# Out.net
KiCad netlist of a schematic drawn in Altium Designer
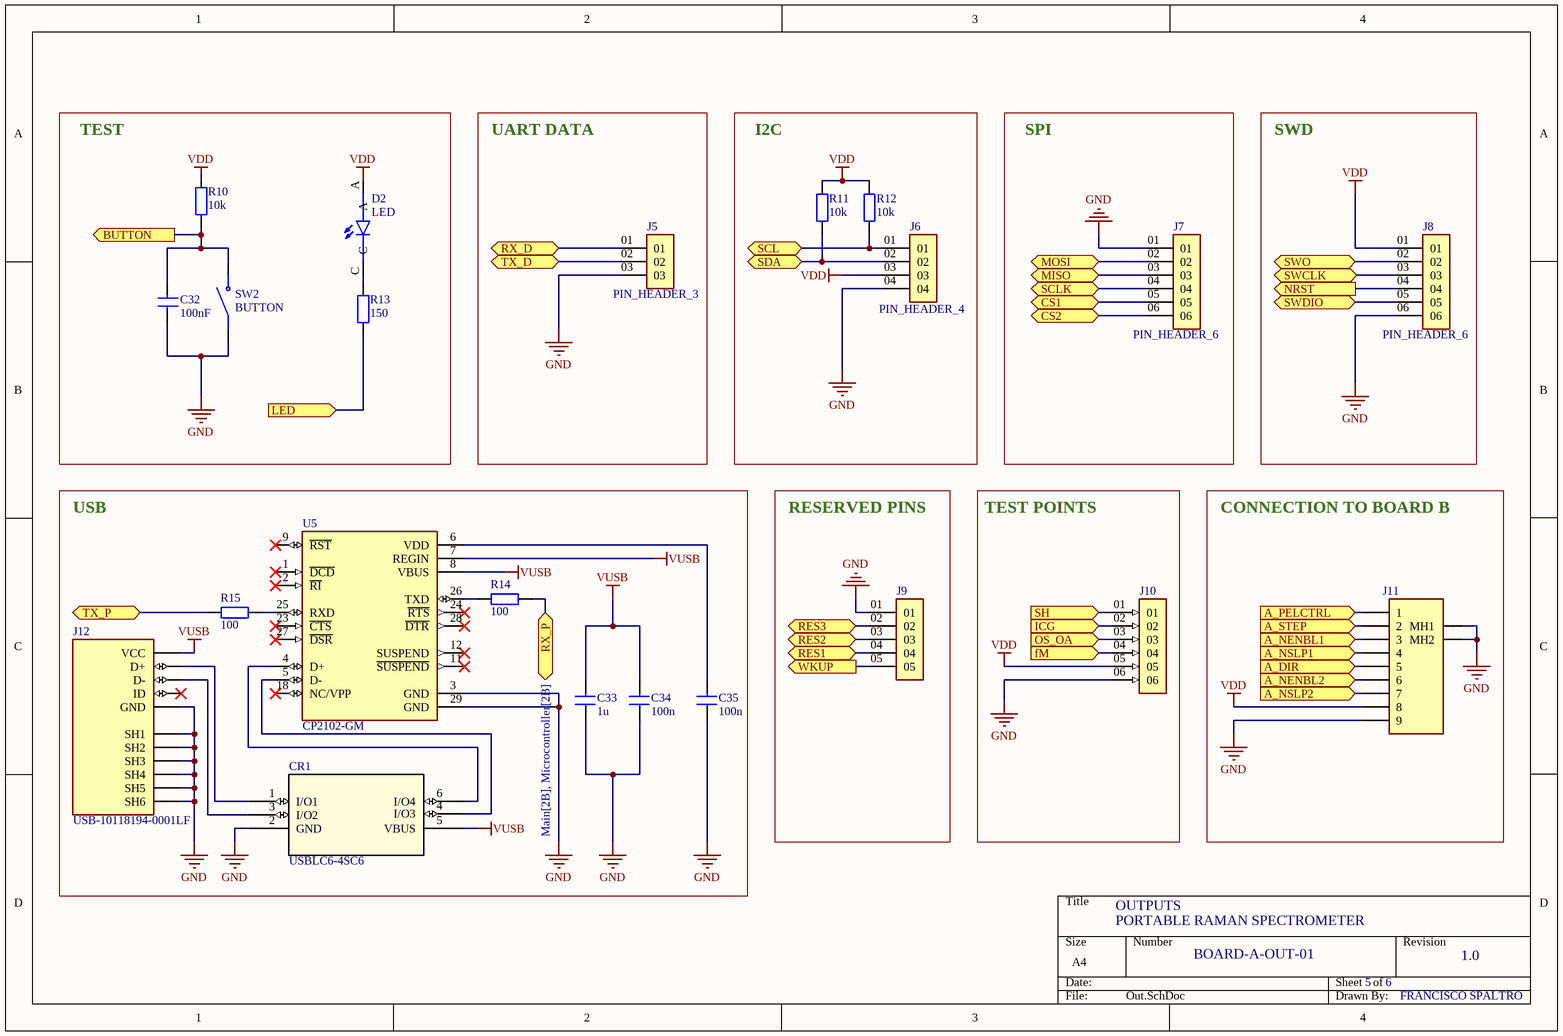
[diagram p0: Out.SchDoc]

(export (version "E")
  (design (tool "Eeschema 10.0.6"))
  (components
    (comp (ref "C32")
      (value "100nF")
      (footprint "RES_0805")
      (description "Generic Capacitor")
      (libsource (lib "Components") (part "CAP_0805"))
    )
    (comp (ref "C33")
      (value "1u")
      (footprint "RES_0805")
      (description "Generic Capacitor")
      (libsource (lib "") (part "CAP_0805_1"))
    )
    (comp (ref "C34")
      (value "100n")
      (footprint "RES_0805")
      (description "Generic Capacitor")
      (libsource (lib "") (part "CAP_0805_1"))
    )
    (comp (ref "C35")
      (value "100n")
      (footprint "RES_0805")
      (description "Generic Capacitor")
      (libsource (lib "") (part "CAP_0805_1"))
    )
    (comp (ref "CR1")
      (value "USBLC6-4SC6")
      (footprint "SOT23-6L_STM-M")
      (description "Very low capacitance ESD protection")
      (fields (field (name "COPYRIGHT") "Copyright (C) 2025 Ultra Librarian. All rights reserved."))
      (libsource (lib "Components") (part "USBLC6-4SC6"))
    )
    (comp (ref "D2")
      (value "LED")
      (footprint "LEDC1608X35N")
      (description "Red 631nm LED Indication - Discrete 2V 0603 (1608 Metric)")
      (fields (field (name "MF") "Lite-On Inc.") (field (name "MP") "LTST-C190KRKT"))
      (libsource (lib "CompAct") (part "LED-LTST-C190KRKT"))
    )
    (comp (ref "J5")
      (value "PIN_HEADER_3")
      (footprint "GEN_PIN3")
      (description "Generic 40 mils drill size, 100 mils step")
      (fields (field (name "MF") "Samtec Inc.") (field (name "MP") "TS-103-T-A"))
      (libsource (lib "Components") (part "PIN_HEADER_3"))
    )
    (comp (ref "J6")
      (value "PIN_HEADER_4")
      (footprint "GEN_PIN4")
      (description "Generic 40 mils drill size, 100 mils step")
      (fields (field (name "MF") "Samtec Inc.") (field (name "MP") "TS-104-T-A"))
      (libsource (lib "Components") (part "PIN_HEADER_4"))
    )
    (comp (ref "J7")
      (value "PIN_HEADER_6")
      (footprint "GEN_PIN6")
      (description "Generic 40 mils drill size, 100 mils step")
      (fields (field (name "MF") "Samtec Inc.") (field (name "MP") "TS-106-T-A"))
      (libsource (lib "Components") (part "PIN_HEADER_6"))
    )
    (comp (ref "J8")
      (value "PIN_HEADER_6")
      (footprint "GEN_PIN6")
      (description "Generic 40 mils drill size, 100 mils step")
      (fields (field (name "MF") "Samtec Inc.") (field (name "MP") "TS-106-T-A"))
      (libsource (lib "Components") (part "PIN_HEADER_6"))
    )
    (comp (ref "J9")
      (value "PIN_HEADER_5")
      (footprint "Components:GEN_PIN5")
      (description "Generic 40 mils drill size, 100 mils step")
      (fields (field (name "MF") "Samtec Inc.") (field (name "MP") "TS-105-T-A"))
      (libsource (lib "Components") (part "PIN_HEADER_5"))
    )
    (comp (ref "J10")
      (value "PIN_HEADER_6")
      (footprint "GEN_PIN6")
      (description "Generic 40 mils drill size, 100 mils step")
      (fields (field (name "MF") "Samtec Inc.") (field (name "MP") "TS-106-T-A"))
      (libsource (lib "Components") (part "PIN_HEADER_6"))
    )
    (comp (ref "J11")
      (value "Phoenix9V_1821465")
      (footprint "PHOENIX_1821465")
      (fields (field (name "MF") "{'manufacturer': u'Phoenix Contact'}") (field (name "MP") "1821465"))
      (libsource (lib "Components") (part "Phoenix9V_1821465"))
    )
    (comp (ref "J12")
      (value "USB-10118194-0001LF")
      (footprint "AMPHENOL_10118194-0001LF")
      (description "Micro USB, Input Output Connectors, B TYPE RECEPTACLE with flange")
      (fields (field (name "MF") "Amphenol ICC") (field (name "MP") "10118194-0001LF"))
      (libsource (lib "Components") (part "USB-10118194-0001LF"))
    )
    (comp (ref "R10")
      (value "10k")
      (footprint "RES_0805")
      (description "Generic Capacitor")
      (libsource (lib "Components") (part "RES_0805"))
    )
    (comp (ref "R11")
      (value "10k")
      (footprint "RES_0805")
      (description "Generic Capacitor")
      (libsource (lib "Components") (part "RES_0805"))
    )
    (comp (ref "R12")
      (value "10k")
      (footprint "RES_0805")
      (description "Generic Capacitor")
      (libsource (lib "Components") (part "RES_0805"))
    )
    (comp (ref "R13")
      (value "150")
      (footprint "RES_0805")
      (description "Generic Capacitor")
      (libsource (lib "Components") (part "RES_0805"))
    )
    (comp (ref "R14")
      (value "100")
      (footprint "RES_0805")
      (description "Generic Capacitor")
      (libsource (lib "Components") (part "RES_0805"))
    )
    (comp (ref "R15")
      (value "100")
      (footprint "RES_0805")
      (description "Generic Capacitor")
      (libsource (lib "Components") (part "RES_0805"))
    )
    (comp (ref "SW2")
      (value "BUTTON")
      (footprint "Components:SW_B3U-1000P")
      (description "Switch Tactile N.O. SPST Round Button Gull Wing 0.05A 12VDC 1.5N SMD Embossed T/R")
      (fields (field (name "MP") "B3U-1000P"))
      (libsource (lib "Components") (part "SW-B3U-1000P"))
    )
    (comp (ref "U5")
      (value "CP2102-GM")
      (footprint "QFN50P500X500X100-29N")
      (description "USB Bridge, USB to UART USB 2.0 UART Interface 28-QFN (5x5)")
      (fields (field (name "MF") "Silicon Labs"))
      (libsource (lib "Components") (part "CP2102-GM"))
    )
  )
  (nets
    (net (code "1") (name "/A_DIR") (class "Default")
      (node (ref "J11") (pin "5") (pinfunction "5_5") (pintype "passive"))
    )
    (net (code "2") (name "/A_NENBL1") (class "Default")
      (node (ref "J11") (pin "3") (pinfunction "3_3") (pintype "passive"))
    )
    (net (code "3") (name "/A_NENBL2") (class "Default")
      (node (ref "J11") (pin "6") (pinfunction "6_6") (pintype "passive"))
    )
    (net (code "4") (name "/A_NSLP1") (class "Default")
      (node (ref "J11") (pin "4") (pinfunction "4_4") (pintype "passive"))
    )
    (net (code "5") (name "/A_NSLP2") (class "Default")
      (node (ref "J11") (pin "7") (pinfunction "7_7") (pintype "passive"))
    )
    (net (code "6") (name "/A_PELCTRL") (class "Default")
      (node (ref "J11") (pin "1") (pinfunction "1_1") (pintype "passive"))
    )
    (net (code "7") (name "/A_STEP") (class "Default")
      (node (ref "J11") (pin "2") (pinfunction "2_2") (pintype "passive"))
    )
    (net (code "8") (name "/BUTTON") (class "Default")
      (node (ref "C32") (pin "1") (pinfunction "1_1") (pintype "passive"))
      (node (ref "R10") (pin "1") (pinfunction "1_1") (pintype "passive"))
      (node (ref "SW2") (pin "2") (pinfunction "2_2") (pintype "passive"))
    )
    (net (code "9") (name "/CS1") (class "Default")
      (node (ref "J7") (pin "05") (pinfunction "05_05") (pintype "input"))
    )
    (net (code "10") (name "/CS2") (class "Default")
      (node (ref "J7") (pin "06") (pinfunction "06_06") (pintype "input"))
    )
    (net (code "11") (name "/ICG") (class "Default")
      (node (ref "J10") (pin "02") (pinfunction "02_02") (pintype "input"))
    )
    (net (code "12") (name "/LED") (class "Default")
      (node (ref "R13") (pin "1") (pinfunction "1_1") (pintype "passive"))
    )
    (net (code "13") (name "/MISO") (class "Default")
      (node (ref "J7") (pin "03") (pinfunction "03_03") (pintype "input"))
    )
    (net (code "14") (name "/MOSI") (class "Default")
      (node (ref "J7") (pin "02") (pinfunction "02_02") (pintype "input"))
    )
    (net (code "15") (name "/NRST") (class "Default")
      (node (ref "J8") (pin "04") (pinfunction "04_04") (pintype "input"))
    )
    (net (code "16") (name "/OS_OA") (class "Default")
      (node (ref "J10") (pin "03") (pinfunction "03_03") (pintype "input"))
    )
    (net (code "17") (name "/RES1") (class "Default")
      (node (ref "J9") (pin "04") (pinfunction "04_04") (pintype "passive"))
    )
    (net (code "18") (name "/RES2") (class "Default")
      (node (ref "J9") (pin "03") (pinfunction "03_03") (pintype "passive"))
    )
    (net (code "19") (name "/RES3") (class "Default")
      (node (ref "J9") (pin "02") (pinfunction "02_02") (pintype "passive"))
    )
    (net (code "20") (name "/RX_D") (class "Default")
      (node (ref "J5") (pin "01") (pinfunction "01_01") (pintype "passive"))
    )
    (net (code "21") (name "/RX_P") (class "Default")
      (node (ref "R14") (pin "2") (pinfunction "2_2") (pintype "passive"))
    )
    (net (code "22") (name "/SCL") (class "Default")
      (node (ref "J6") (pin "01") (pinfunction "01_01") (pintype "passive"))
      (node (ref "R12") (pin "1") (pinfunction "1_1") (pintype "passive"))
    )
    (net (code "23") (name "/SCLK") (class "Default")
      (node (ref "J7") (pin "04") (pinfunction "04_04") (pintype "input"))
    )
    (net (code "24") (name "/SDA") (class "Default")
      (node (ref "J6") (pin "02") (pinfunction "02_02") (pintype "passive"))
      (node (ref "R11") (pin "1") (pinfunction "1_1") (pintype "passive"))
    )
    (net (code "25") (name "/SH") (class "Default")
      (node (ref "J10") (pin "01") (pinfunction "01_01") (pintype "input"))
    )
    (net (code "26") (name "/SWCLK") (class "Default")
      (node (ref "J8") (pin "03") (pinfunction "03_03") (pintype "input"))
    )
    (net (code "27") (name "/SWDIO") (class "Default")
      (node (ref "J8") (pin "05") (pinfunction "05_05") (pintype "input"))
    )
    (net (code "28") (name "/SWO") (class "Default")
      (node (ref "J8") (pin "02") (pinfunction "02_02") (pintype "input"))
    )
    (net (code "29") (name "/TX_D") (class "Default")
      (node (ref "J5") (pin "02") (pinfunction "02_02") (pintype "passive"))
    )
    (net (code "30") (name "/TX_P") (class "Default")
      (node (ref "R15") (pin "1") (pinfunction "1_1") (pintype "passive"))
    )
    (net (code "31") (name "/WKUP") (class "Default")
      (node (ref "J9") (pin "05") (pinfunction "05_05") (pintype "passive"))
    )
    (net (code "32") (name "/fM") (class "Default")
      (node (ref "J10") (pin "04") (pinfunction "04_04") (pintype "input"))
    )
    (net (code "33") (name "GND") (class "Default")
      (node (ref "C32") (pin "2") (pinfunction "2_2") (pintype "passive"))
      (node (ref "C33") (pin "1") (pinfunction "1_1") (pintype "passive"))
      (node (ref "C34") (pin "1") (pinfunction "1_1") (pintype "passive"))
      (node (ref "C35") (pin "1") (pinfunction "1_1") (pintype "passive"))
      (node (ref "CR1") (pin "2") (pinfunction "GND_2") (pintype "power_in"))
      (node (ref "J10") (pin "06") (pinfunction "06_06") (pintype "input"))
      (node (ref "J11") (pin "9") (pinfunction "9_9") (pintype "passive"))
      (node (ref "J11") (pin "MH1") (pinfunction "MH1_MH1") (pintype "passive"))
      (node (ref "J11") (pin "MH2") (pinfunction "MH2_MH2") (pintype "passive"))
      (node (ref "J12") (pin "5") (pinfunction "GND_5") (pintype "power_in"))
      (node (ref "J12") (pin "SH1") (pinfunction "SH1_SH1") (pintype "passive"))
      (node (ref "J12") (pin "SH2") (pinfunction "SH2_SH2") (pintype "passive"))
      (node (ref "J12") (pin "SH3") (pinfunction "SH3_SH3") (pintype "passive"))
      (node (ref "J12") (pin "SH4") (pinfunction "SH4_SH4") (pintype "passive"))
      (node (ref "J12") (pin "SH5") (pinfunction "SH5_SH5") (pintype "passive"))
      (node (ref "J12") (pin "SH6") (pinfunction "SH6_SH6") (pintype "passive"))
      (node (ref "J5") (pin "03") (pinfunction "03_03") (pintype "passive"))
      (node (ref "J6") (pin "04") (pinfunction "04_04") (pintype "passive"))
      (node (ref "J7") (pin "01") (pinfunction "01_01") (pintype "input"))
      (node (ref "J8") (pin "06") (pinfunction "06_06") (pintype "input"))
      (node (ref "J9") (pin "01") (pinfunction "01_01") (pintype "passive"))
      (node (ref "SW2") (pin "1") (pinfunction "1_1") (pintype "passive"))
      (node (ref "U5") (pin "29") (pinfunction "GND_29") (pintype "power_in"))
      (node (ref "U5") (pin "3") (pinfunction "GND_3") (pintype "power_in"))
    )
    (net (code "34") (name "Net-(CR1-I{slash}O1)") (class "Default")
      (node (ref "CR1") (pin "1") (pinfunction "I/O1_1") (pintype "bidirectional"))
      (node (ref "J12") (pin "3") (pinfunction "D+_3") (pintype "bidirectional"))
    )
    (net (code "35") (name "Net-(CR1-I{slash}O2)") (class "Default")
      (node (ref "CR1") (pin "3") (pinfunction "I/O2_3") (pintype "bidirectional"))
      (node (ref "J12") (pin "2") (pinfunction "D-_2") (pintype "bidirectional"))
    )
    (net (code "36") (name "Net-(CR1-I{slash}O3)") (class "Default")
      (node (ref "CR1") (pin "4") (pinfunction "I/O3_4") (pintype "bidirectional"))
      (node (ref "U5") (pin "5") (pinfunction "D-_5") (pintype "bidirectional"))
    )
    (net (code "37") (name "Net-(CR1-I{slash}O4)") (class "Default")
      (node (ref "CR1") (pin "6") (pinfunction "I/O4_6") (pintype "bidirectional"))
      (node (ref "U5") (pin "4") (pinfunction "D+_4") (pintype "bidirectional"))
    )
    (net (code "38") (name "Net-(D2-PadC)") (class "Default")
      (node (ref "D2") (pin "C") (pinfunction "C_C") (pintype "passive"))
      (node (ref "R13") (pin "2") (pinfunction "2_2") (pintype "passive"))
    )
    (net (code "39") (name "Net-(U5-RXD)") (class "Default")
      (node (ref "R15") (pin "2") (pinfunction "2_2") (pintype "passive"))
      (node (ref "U5") (pin "25") (pinfunction "RXD_25") (pintype "bidirectional"))
    )
    (net (code "40") (name "Net-(U5-TXD)") (class "Default")
      (node (ref "R14") (pin "1") (pinfunction "1_1") (pintype "passive"))
      (node (ref "U5") (pin "26") (pinfunction "TXD_26") (pintype "bidirectional"))
    )
    (net (code "41") (name "Net-(U5-VDD)") (class "Default")
      (node (ref "C35") (pin "2") (pinfunction "2_2") (pintype "passive"))
      (node (ref "U5") (pin "6") (pinfunction "VDD_6") (pintype "power_in"))
    )
    (net (code "42") (name "VDD") (class "Default")
      (node (ref "D2") (pin "A") (pinfunction "A_A") (pintype "passive"))
      (node (ref "J10") (pin "05") (pinfunction "05_05") (pintype "input"))
      (node (ref "J11") (pin "8") (pinfunction "8_8") (pintype "passive"))
      (node (ref "J6") (pin "03") (pinfunction "03_03") (pintype "passive"))
      (node (ref "J8") (pin "01") (pinfunction "01_01") (pintype "input"))
      (node (ref "R10") (pin "2") (pinfunction "2_2") (pintype "passive"))
      (node (ref "R11") (pin "2") (pinfunction "2_2") (pintype "passive"))
      (node (ref "R12") (pin "2") (pinfunction "2_2") (pintype "passive"))
    )
    (net (code "43") (name "VUSB") (class "Default")
      (node (ref "C33") (pin "2") (pinfunction "2_2") (pintype "passive"))
      (node (ref "C34") (pin "2") (pinfunction "2_2") (pintype "passive"))
      (node (ref "CR1") (pin "5") (pinfunction "VBUS_5") (pintype "power_in"))
      (node (ref "J12") (pin "1") (pinfunction "VCC_1") (pintype "power_in"))
      (node (ref "U5") (pin "7") (pinfunction "REGIN_7") (pintype "power_in"))
      (node (ref "U5") (pin "8") (pinfunction "VBUS_8") (pintype "power_in"))
    )
    (net (code "44") (name "unconnected-(J12-ID-Pad4)") (class "Default")
      (node (ref "J12") (pin "4") (pinfunction "ID_4") (pintype "bidirectional+no_connect"))
    )
    (net (code "45") (name "unconnected-(U5-NC{slash}VPP-Pad18)") (class "Default")
      (node (ref "U5") (pin "18") (pinfunction "NC/VPP_18") (pintype "bidirectional+no_connect"))
    )
    (net (code "46") (name "unconnected-(U5-SUSPEND-Pad12)") (class "Default")
      (node (ref "U5") (pin "12") (pinfunction "SUSPEND_12") (pintype "output+no_connect"))
    )
    (net (code "47") (name "unconnected-(U5-~{CTS}-Pad23)") (class "Default")
      (node (ref "U5") (pin "23") (pinfunction "~{CTS}_23") (pintype "input+no_connect"))
    )
    (net (code "48") (name "unconnected-(U5-~{DCD}-Pad1)") (class "Default")
      (node (ref "U5") (pin "1") (pinfunction "~{DCD}_1") (pintype "input+no_connect"))
    )
    (net (code "49") (name "unconnected-(U5-~{DSR}-Pad27)") (class "Default")
      (node (ref "U5") (pin "27") (pinfunction "~{DSR}_27") (pintype "input+no_connect"))
    )
    (net (code "50") (name "unconnected-(U5-~{DTR}-Pad28)") (class "Default")
      (node (ref "U5") (pin "28") (pinfunction "~{DTR}_28") (pintype "output+no_connect"))
    )
    (net (code "51") (name "unconnected-(U5-~{RI}-Pad2)") (class "Default")
      (node (ref "U5") (pin "2") (pinfunction "~{RI}_2") (pintype "input+no_connect"))
    )
    (net (code "52") (name "unconnected-(U5-~{RST}-Pad9)") (class "Default")
      (node (ref "U5") (pin "9") (pinfunction "~{RST}_9") (pintype "bidirectional+no_connect"))
    )
    (net (code "53") (name "unconnected-(U5-~{RTS}-Pad24)") (class "Default")
      (node (ref "U5") (pin "24") (pinfunction "~{RTS}_24") (pintype "output+no_connect"))
    )
    (net (code "54") (name "unconnected-(U5-~{SUSPEND}-Pad11)") (class "Default")
      (node (ref "U5") (pin "11") (pinfunction "~{SUSPEND}_11") (pintype "output+no_connect"))
    )
  )
)
